# smartee_main.net
KiCad netlist of a schematic drawn in Altium Designer
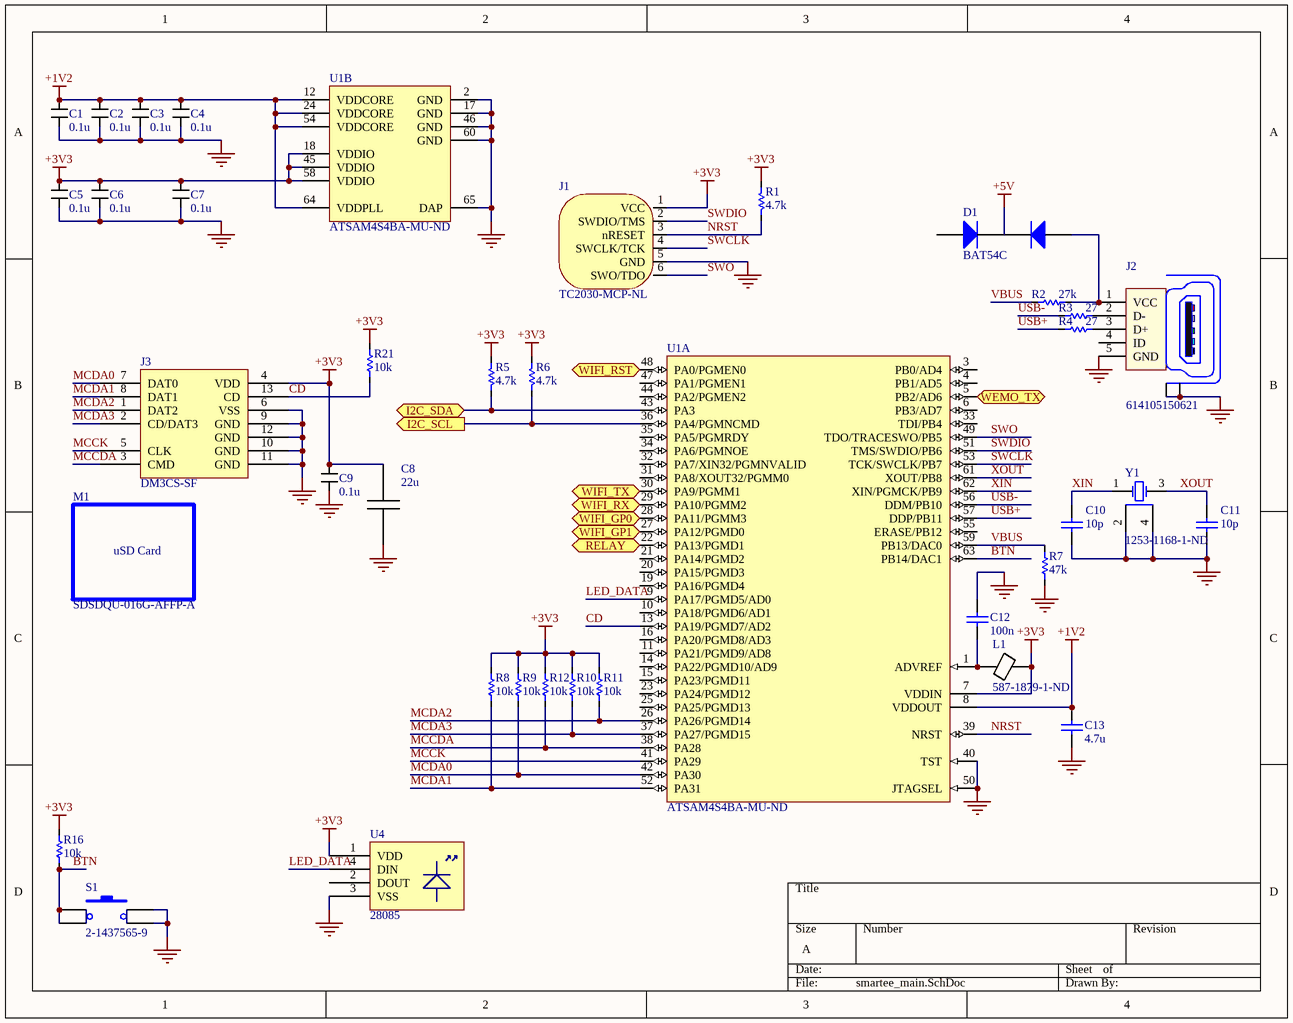
[diagram p0: smartee_main.SchDoc]

(export (version "E")
  (design (tool "Eeschema 10.0.6"))
  (components
    (comp (ref "C1")
      (value "0.1u")
      (footprint "R0603")
      (description "CAP CER 0.1UF 50V Y5V 0603")
      (fields
        (field (name "MANUFACTURER") "Yageo")
        (field (name "MANUFACTURER PART NUMBER") "CC0603ZRY5V9BB104")
      )
      (libsource (lib "NILM Library") (part "CC0603ZRY5V9BB104"))
    )
    (comp (ref "C2")
      (value "0.1u")
      (footprint "R0603")
      (description "CAP CER 0.1UF 50V Y5V 0603")
      (fields
        (field (name "MANUFACTURER") "Yageo")
        (field (name "MANUFACTURER PART NUMBER") "CC0603ZRY5V9BB104")
      )
      (libsource (lib "NILM Library") (part "CC0603ZRY5V9BB104"))
    )
    (comp (ref "C3")
      (value "0.1u")
      (footprint "R0603")
      (description "CAP CER 0.1UF 50V Y5V 0603")
      (fields
        (field (name "MANUFACTURER") "Yageo")
        (field (name "MANUFACTURER PART NUMBER") "CC0603ZRY5V9BB104")
      )
      (libsource (lib "NILM Library") (part "CC0603ZRY5V9BB104"))
    )
    (comp (ref "C4")
      (value "0.1u")
      (footprint "R0603")
      (description "CAP CER 0.1UF 50V Y5V 0603")
      (fields
        (field (name "MANUFACTURER") "Yageo")
        (field (name "MANUFACTURER PART NUMBER") "CC0603ZRY5V9BB104")
      )
      (libsource (lib "NILM Library") (part "CC0603ZRY5V9BB104"))
    )
    (comp (ref "C5")
      (value "0.1u")
      (footprint "R0603")
      (description "CAP CER 0.1UF 50V Y5V 0603")
      (fields
        (field (name "MANUFACTURER") "Yageo")
        (field (name "MANUFACTURER PART NUMBER") "CC0603ZRY5V9BB104")
      )
      (libsource (lib "NILM Library") (part "CC0603ZRY5V9BB104"))
    )
    (comp (ref "C6")
      (value "0.1u")
      (footprint "R0603")
      (description "CAP CER 0.1UF 50V Y5V 0603")
      (fields
        (field (name "MANUFACTURER") "Yageo")
        (field (name "MANUFACTURER PART NUMBER") "CC0603ZRY5V9BB104")
      )
      (libsource (lib "NILM Library") (part "CC0603ZRY5V9BB104"))
    )
    (comp (ref "C7")
      (value "0.1u")
      (footprint "R0603")
      (description "CAP CER 0.1UF 50V Y5V 0603")
      (fields
        (field (name "MANUFACTURER") "Yageo")
        (field (name "MANUFACTURER PART NUMBER") "CC0603ZRY5V9BB104")
      )
      (libsource (lib "NILM Library") (part "CC0603ZRY5V9BB104"))
    )
    (comp (ref "C8")
      (value "22u")
      (footprint "0805")
      (description "CAP CER 22UF 25V 20% X5R 0805")
      (fields
        (field (name "MANUFACTURER") "Samsung Electro-Mechanics America, Inc")
        (field (name "MANUFACTURER PART NUMBER") "CL21A226MAQNNNE")
      )
      (libsource (lib "NILM Library") (part "CL21A226MAQNNNE"))
    )
    (comp (ref "C9")
      (value "0.1u")
      (footprint "R0603")
      (description "CAP CER 0.1UF 50V Y5V 0603")
      (fields
        (field (name "MANUFACTURER") "Yageo")
        (field (name "MANUFACTURER PART NUMBER") "CC0603ZRY5V9BB104")
      )
      (libsource (lib "NILM Library") (part "CC0603ZRY5V9BB104"))
    )
    (comp (ref "C10")
      (value "10p")
      (footprint "0603")
      (description "Capacitor")
      (fields (field (name "Comment") "CAP") (field (name "PUBLISHER") "Altium Limited"))
      (libsource (lib "nilm") (part "CAP"))
    )
    (comp (ref "C11")
      (value "10p")
      (footprint "0603")
      (description "Capacitor")
      (fields (field (name "Comment") "CAP") (field (name "PUBLISHER") "Altium Limited"))
      (libsource (lib "nilm") (part "CAP"))
    )
    (comp (ref "C12")
      (value "100n")
      (footprint "0603")
      (description "Capacitor")
      (fields (field (name "Comment") "CAP") (field (name "PUBLISHER") "Altium Limited"))
      (libsource (lib "nilm") (part "CAP"))
    )
    (comp (ref "C13")
      (value "4.7u")
      (footprint "0603")
      (description "Capacitor")
      (fields (field (name "Comment") "CAP") (field (name "PUBLISHER") "Altium Limited"))
      (libsource (lib "nilm") (part "CAP"))
    )
    (comp (ref "D1")
      (value "BAT54C")
      (footprint "SOT23")
      (description "DIODE SCHOTTKY 30V 200MA SOT23")
      (fields (field (name "MANUFACTURER") "Fairchild Semiconductor"))
      (libsource (lib "NILM Library") (part "BAT54C"))
    )
    (comp (ref "J1")
      (value "TC2030-MCP-NL")
      (footprint "TC2030-MCP-NL")
      (description "Tag Connect")
      (libsource (lib "TC2030") (part "TC2030-MCP-NL"))
    )
    (comp (ref "J2")
      (value "614105150621")
      (footprint "614105150621")
      (description "CONN RCPT USB TYPE AB")
      (fields (field (name "MANUFACTURER") "Wurth Electronics Inc"))
      (libsource (lib "NILM Library") (part "614105150621"))
    )
    (comp (ref "J3")
      (value "DM3CS-SF")
      (footprint "DM3CS-SF")
      (description "CONN MICRO SD R/A HING TYPE SMD")
      (fields (field (name "MANUFACTURER") "Hirose Electric Co Ltd"))
      (libsource (lib "NILM Library") (part "DM3CS-SF"))
    )
    (comp (ref "L1")
      (value "Ferrite")
      (footprint "0603")
      (description "Ferrite bead")
      (fields
        (field (name "SUPPLIER PART NUMBER 1") "587-1879-1-ND")
        (field (name "PUBLISHER") "Altium Limited")
      )
      (libsource (lib "nilm") (part "Ferrite"))
    )
    (comp (ref "M1")
      (value "SDSDQU-016G-AFFP-A")
      (description "16 GB uSD Card")
      (libsource (lib "NILM Library") (part "uSD Card"))
    )
    (comp (ref "R1")
      (value "4.7k")
      (footprint "0603")
      (description "Resistor")
      (fields (field (name "Comment") "RES") (field (name "PUBLISHER") "Altium Limited"))
      (libsource (lib "nilm") (part "RES"))
    )
    (comp (ref "R2")
      (value "27k")
      (footprint "0603")
      (description "Resistor")
      (fields (field (name "Comment") "RES") (field (name "PUBLISHER") "Altium Limited"))
      (libsource (lib "nilm") (part "RES"))
    )
    (comp (ref "R3")
      (value "27")
      (footprint "0603")
      (description "Resistor")
      (fields (field (name "Comment") "RES") (field (name "PUBLISHER") "Altium Limited"))
      (libsource (lib "nilm") (part "RES"))
    )
    (comp (ref "R4")
      (value "27")
      (footprint "0603")
      (description "Resistor")
      (fields (field (name "Comment") "RES") (field (name "PUBLISHER") "Altium Limited"))
      (libsource (lib "nilm") (part "RES"))
    )
    (comp (ref "R5")
      (value "4.7k")
      (footprint "0603")
      (description "Resistor")
      (fields (field (name "Comment") "RES") (field (name "PUBLISHER") "Altium Limited"))
      (libsource (lib "nilm") (part "RES"))
    )
    (comp (ref "R6")
      (value "4.7k")
      (footprint "0603")
      (description "Resistor")
      (fields (field (name "Comment") "RES") (field (name "PUBLISHER") "Altium Limited"))
      (libsource (lib "nilm") (part "RES"))
    )
    (comp (ref "R7")
      (value "47k")
      (footprint "0603")
      (description "Resistor")
      (fields (field (name "Comment") "RES") (field (name "PUBLISHER") "Altium Limited"))
      (libsource (lib "nilm") (part "RES"))
    )
    (comp (ref "R8")
      (value "10k")
      (footprint "0603")
      (description "Resistor")
      (fields (field (name "Comment") "RES") (field (name "PUBLISHER") "Altium Limited"))
      (libsource (lib "nilm") (part "RES"))
    )
    (comp (ref "R9")
      (value "10k")
      (footprint "0603")
      (description "Resistor")
      (fields (field (name "Comment") "RES") (field (name "PUBLISHER") "Altium Limited"))
      (libsource (lib "nilm") (part "RES"))
    )
    (comp (ref "R10")
      (value "10k")
      (footprint "0603")
      (description "Resistor")
      (fields (field (name "Comment") "RES") (field (name "PUBLISHER") "Altium Limited"))
      (libsource (lib "nilm") (part "RES"))
    )
    (comp (ref "R11")
      (value "10k")
      (footprint "0603")
      (description "Resistor")
      (fields (field (name "Comment") "RES") (field (name "PUBLISHER") "Altium Limited"))
      (libsource (lib "nilm") (part "RES"))
    )
    (comp (ref "R12")
      (value "10k")
      (footprint "0603")
      (description "Resistor")
      (fields (field (name "Comment") "RES") (field (name "PUBLISHER") "Altium Limited"))
      (libsource (lib "nilm") (part "RES"))
    )
    (comp (ref "R16")
      (value "10k")
      (footprint "0603")
      (description "Resistor")
      (fields (field (name "Comment") "RES") (field (name "PUBLISHER") "Altium Limited"))
      (libsource (lib "nilm") (part "RES"))
    )
    (comp (ref "R21")
      (value "10k")
      (footprint "0603")
      (description "Resistor")
      (fields (field (name "Comment") "RES") (field (name "PUBLISHER") "Altium Limited"))
      (libsource (lib "nilm") (part "RES"))
    )
    (comp (ref "S1")
      (value "2-1437565-9")
      (footprint "2-1437565-9")
      (description "SWITCH TACTILE SPST-NO 0.05A 12V")
      (fields (field (name "MANUFACTURER") "TE Connectivity"))
      (libsource (lib "NILM Library") (part "2-1437565-9"))
    )
    (comp (ref "U1")
      (value "SAM4S")
      (footprint "nilm:QFN64")
      (description "Atmel SAM4S microcontroller, 64 pin")
      (fields (field (name "SUPPLIER PART NUMBER 1") "ATSAM4S4BA-MU-ND"))
      (libsource (lib "nilm") (part "SAM4S"))
    )
    (comp (ref "U4")
      (value "28085")
      (footprint "WS2812B")
      (description "WS2812 LED MODULE")
      (fields (field (name "MANUFACTURER") "Parallax Inc"))
      (libsource (lib "NILM Library") (part "28085"))
    )
    (comp (ref "Y1")
      (value "XTAL")
      (footprint "XTAL_3.2x2.5mm")
      (description "Crystal Oscillator")
      (fields
        (field (name "SUPPLIER PART NUMBER 1") "1253-1168-1-ND")
        (field (name "PUBLISHER") "Altium Limited")
      )
      (libsource (lib "nilm") (part "XTAL"))
    )
  )
  (nets
    (net (code "1") (name "+1V2") (class "Default")
      (node (ref "C1") (pin "1") (pinfunction "1_1") (pintype "passive"))
      (node (ref "C13") (pin "2") (pinfunction "2_2") (pintype "passive"))
      (node (ref "C2") (pin "1") (pinfunction "1_1") (pintype "passive"))
      (node (ref "C3") (pin "1") (pinfunction "1_1") (pintype "passive"))
      (node (ref "C4") (pin "1") (pinfunction "1_1") (pintype "passive"))
      (node (ref "U1") (pin "12") (pinfunction "VDDCORE_12") (pintype "power_in"))
      (node (ref "U1") (pin "24") (pinfunction "VDDCORE_24") (pintype "power_in"))
      (node (ref "U1") (pin "54") (pinfunction "VDDCORE_54") (pintype "power_in"))
      (node (ref "U1") (pin "64") (pinfunction "VDDPLL_64") (pintype "power_in"))
      (node (ref "U1") (pin "8") (pinfunction "VDDOUT_8") (pintype "power_in"))
    )
    (net (code "2") (name "+3V3") (class "Default")
      (node (ref "C5") (pin "1") (pinfunction "1_1") (pintype "passive"))
      (node (ref "C6") (pin "1") (pinfunction "1_1") (pintype "passive"))
      (node (ref "C7") (pin "1") (pinfunction "1_1") (pintype "passive"))
      (node (ref "C8") (pin "1") (pinfunction "1_1") (pintype "passive"))
      (node (ref "C9") (pin "1") (pinfunction "1_1") (pintype "passive"))
      (node (ref "J1") (pin "1") (pinfunction "VCC_1") (pintype "passive"))
      (node (ref "J3") (pin "4") (pinfunction "VDD_4") (pintype "passive"))
      (node (ref "L1") (pin "1") (pinfunction "1_1") (pintype "passive"))
      (node (ref "R1") (pin "1") (pinfunction "1_1") (pintype "passive"))
      (node (ref "R10") (pin "2") (pinfunction "2_2") (pintype "passive"))
      (node (ref "R11") (pin "2") (pinfunction "2_2") (pintype "passive"))
      (node (ref "R12") (pin "2") (pinfunction "2_2") (pintype "passive"))
      (node (ref "R16") (pin "2") (pinfunction "2_2") (pintype "passive"))
      (node (ref "R21") (pin "2") (pinfunction "2_2") (pintype "passive"))
      (node (ref "R5") (pin "1") (pinfunction "1_1") (pintype "passive"))
      (node (ref "R6") (pin "1") (pinfunction "1_1") (pintype "passive"))
      (node (ref "R8") (pin "2") (pinfunction "2_2") (pintype "passive"))
      (node (ref "R9") (pin "2") (pinfunction "2_2") (pintype "passive"))
      (node (ref "U1") (pin "18") (pinfunction "VDDIO_18") (pintype "power_in"))
      (node (ref "U1") (pin "45") (pinfunction "VDDIO_45") (pintype "power_in"))
      (node (ref "U1") (pin "58") (pinfunction "VDDIO_58") (pintype "power_in"))
      (node (ref "U1") (pin "7") (pinfunction "VDDIN_7") (pintype "power_in"))
      (node (ref "U4") (pin "1") (pinfunction "VDD_1") (pintype "passive"))
    )
    (net (code "3") (name "+5V") (class "Default")
      (node (ref "D1") (pin "3") (pinfunction "K_3") (pintype "passive"))
    )
    (net (code "4") (name "/BTN") (class "Default")
      (node (ref "R16") (pin "1") (pinfunction "1_1") (pintype "passive"))
      (node (ref "S1") (pin "1") (pinfunction "1_1") (pintype "passive"))
      (node (ref "S1") (pin "2") (pinfunction "2_2") (pintype "passive"))
      (node (ref "U1") (pin "63") (pinfunction "PB14/DAC1_63") (pintype "bidirectional"))
    )
    (net (code "5") (name "/CD") (class "Default")
      (node (ref "J3") (pin "13") (pinfunction "CD_13") (pintype "passive"))
      (node (ref "R21") (pin "1") (pinfunction "1_1") (pintype "passive"))
      (node (ref "U1") (pin "13") (pinfunction "PA19/PGMD7/AD2_13") (pintype "bidirectional"))
    )
    (net (code "6") (name "/I2C_SCL") (class "Default")
      (node (ref "R6") (pin "2") (pinfunction "2_2") (pintype "passive"))
      (node (ref "U1") (pin "36") (pinfunction "PA4/PGMNCMD_36") (pintype "bidirectional"))
    )
    (net (code "7") (name "/I2C_SDA") (class "Default")
      (node (ref "R5") (pin "2") (pinfunction "2_2") (pintype "passive"))
      (node (ref "U1") (pin "43") (pinfunction "PA3_43") (pintype "bidirectional"))
    )
    (net (code "8") (name "/LED_DATA") (class "Default")
      (node (ref "U1") (pin "9") (pinfunction "PA17/PGMD5/AD0_9") (pintype "bidirectional"))
      (node (ref "U4") (pin "4") (pinfunction "DIN_4") (pintype "passive"))
    )
    (net (code "9") (name "/MCCDA") (class "Default")
      (node (ref "J3") (pin "3") (pinfunction "CMD_3") (pintype "passive"))
      (node (ref "R12") (pin "1") (pinfunction "1_1") (pintype "passive"))
      (node (ref "U1") (pin "38") (pinfunction "PA28_38") (pintype "bidirectional"))
    )
    (net (code "10") (name "/MCCK") (class "Default")
      (node (ref "J3") (pin "5") (pinfunction "CLK_5") (pintype "passive"))
      (node (ref "U1") (pin "41") (pinfunction "PA29_41") (pintype "bidirectional"))
    )
    (net (code "11") (name "/MCDA0") (class "Default")
      (node (ref "J3") (pin "7") (pinfunction "DAT0_7") (pintype "passive"))
      (node (ref "R9") (pin "1") (pinfunction "1_1") (pintype "passive"))
      (node (ref "U1") (pin "42") (pinfunction "PA30_42") (pintype "bidirectional"))
    )
    (net (code "12") (name "/MCDA1") (class "Default")
      (node (ref "J3") (pin "8") (pinfunction "DAT1_8") (pintype "passive"))
      (node (ref "R8") (pin "1") (pinfunction "1_1") (pintype "passive"))
      (node (ref "U1") (pin "52") (pinfunction "PA31_52") (pintype "bidirectional"))
    )
    (net (code "13") (name "/MCDA2") (class "Default")
      (node (ref "J3") (pin "1") (pinfunction "DAT2_1") (pintype "passive"))
      (node (ref "R11") (pin "1") (pinfunction "1_1") (pintype "passive"))
      (node (ref "U1") (pin "26") (pinfunction "PA26/PGMD14_26") (pintype "bidirectional"))
    )
    (net (code "14") (name "/MCDA3") (class "Default")
      (node (ref "J3") (pin "2") (pinfunction "CD/DAT3_2") (pintype "passive"))
      (node (ref "R10") (pin "1") (pinfunction "1_1") (pintype "passive"))
      (node (ref "U1") (pin "37") (pinfunction "PA27/PGMD15_37") (pintype "bidirectional"))
    )
    (net (code "15") (name "/NRST") (class "Default")
      (node (ref "J1") (pin "3") (pinfunction "nRESET_3") (pintype "passive"))
      (node (ref "R1") (pin "2") (pinfunction "2_2") (pintype "passive"))
      (node (ref "U1") (pin "39") (pinfunction "NRST_39") (pintype "bidirectional"))
    )
    (net (code "16") (name "/RELAY") (class "Default")
      (node (ref "U1") (pin "22") (pinfunction "PA13/PGMD1_22") (pintype "bidirectional"))
    )
    (net (code "17") (name "/SWCLK") (class "Default")
      (node (ref "J1") (pin "4") (pinfunction "SWCLK/TCK_4") (pintype "passive"))
      (node (ref "U1") (pin "53") (pinfunction "TCK/SWCLK/PB7_53") (pintype "bidirectional"))
    )
    (net (code "18") (name "/SWDIO") (class "Default")
      (node (ref "J1") (pin "2") (pinfunction "SWDIO/TMS_2") (pintype "passive"))
      (node (ref "U1") (pin "51") (pinfunction "TMS/SWDIO/PB6_51") (pintype "bidirectional"))
    )
    (net (code "19") (name "/SWO") (class "Default")
      (node (ref "J1") (pin "6") (pinfunction "SWO/TDO_6") (pintype "passive"))
      (node (ref "U1") (pin "49") (pinfunction "TDO/TRACESWO/PB5_49") (pintype "bidirectional"))
    )
    (net (code "20") (name "/USB+") (class "Default")
      (node (ref "R4") (pin "1") (pinfunction "1_1") (pintype "passive"))
      (node (ref "U1") (pin "57") (pinfunction "DDP/PB11_57") (pintype "bidirectional"))
    )
    (net (code "21") (name "/USB-") (class "Default")
      (node (ref "R3") (pin "1") (pinfunction "1_1") (pintype "passive"))
      (node (ref "U1") (pin "56") (pinfunction "DDM/PB10_56") (pintype "bidirectional"))
    )
    (net (code "22") (name "/VBUS") (class "Default")
      (node (ref "R2") (pin "1") (pinfunction "1_1") (pintype "passive"))
      (node (ref "R7") (pin "2") (pinfunction "2_2") (pintype "passive"))
      (node (ref "U1") (pin "59") (pinfunction "PB13/DAC0_59") (pintype "bidirectional"))
    )
    (net (code "23") (name "/WEMO_TX") (class "Default")
      (node (ref "U1") (pin "5") (pinfunction "PB2/AD6_5") (pintype "bidirectional"))
    )
    (net (code "24") (name "/WIFI_GP0") (class "Default")
      (node (ref "U1") (pin "28") (pinfunction "PA11/PGMM3_28") (pintype "bidirectional"))
    )
    (net (code "25") (name "/WIFI_GP1") (class "Default")
      (node (ref "U1") (pin "27") (pinfunction "PA12/PGMD0_27") (pintype "bidirectional"))
    )
    (net (code "26") (name "/WIFI_RST") (class "Default")
      (node (ref "U1") (pin "48") (pinfunction "PA0/PGMEN0_48") (pintype "bidirectional"))
    )
    (net (code "27") (name "/WIFI_RX") (class "Default")
      (node (ref "U1") (pin "29") (pinfunction "PA10/PGMM2_29") (pintype "bidirectional"))
    )
    (net (code "28") (name "/WIFI_TX") (class "Default")
      (node (ref "U1") (pin "30") (pinfunction "PA9/PGMM1_30") (pintype "bidirectional"))
    )
    (net (code "29") (name "/XIN") (class "Default")
      (node (ref "C10") (pin "2") (pinfunction "2_2") (pintype "passive"))
      (node (ref "U1") (pin "62") (pinfunction "XIN/PGMCK/PB9_62") (pintype "bidirectional"))
      (node (ref "Y1") (pin "1") (pinfunction "OSC1_1") (pintype "passive"))
    )
    (net (code "30") (name "/XOUT") (class "Default")
      (node (ref "C11") (pin "2") (pinfunction "2_2") (pintype "passive"))
      (node (ref "U1") (pin "61") (pinfunction "XOUT/PB8_61") (pintype "bidirectional"))
      (node (ref "Y1") (pin "3") (pinfunction "OSC2_3") (pintype "passive"))
    )
    (net (code "31") (name "GND") (class "Default")
      (node (ref "C1") (pin "2") (pinfunction "2_2") (pintype "passive"))
      (node (ref "C10") (pin "1") (pinfunction "1_1") (pintype "passive"))
      (node (ref "C11") (pin "1") (pinfunction "1_1") (pintype "passive"))
      (node (ref "C12") (pin "2") (pinfunction "2_2") (pintype "passive"))
      (node (ref "C13") (pin "1") (pinfunction "1_1") (pintype "passive"))
      (node (ref "C2") (pin "2") (pinfunction "2_2") (pintype "passive"))
      (node (ref "C3") (pin "2") (pinfunction "2_2") (pintype "passive"))
      (node (ref "C4") (pin "2") (pinfunction "2_2") (pintype "passive"))
      (node (ref "C5") (pin "2") (pinfunction "2_2") (pintype "passive"))
      (node (ref "C6") (pin "2") (pinfunction "2_2") (pintype "passive"))
      (node (ref "C7") (pin "2") (pinfunction "2_2") (pintype "passive"))
      (node (ref "C8") (pin "2") (pinfunction "2_2") (pintype "passive"))
      (node (ref "C9") (pin "2") (pinfunction "2_2") (pintype "passive"))
      (node (ref "J1") (pin "5") (pinfunction "GND_5") (pintype "passive"))
      (node (ref "J2") (pin "5") (pinfunction "GND_5") (pintype "passive"))
      (node (ref "J2") (pin "Z1") (pinfunction "Shield_Z1") (pintype "passive"))
      (node (ref "J2") (pin "Z2") (pinfunction "Shield_Z2") (pintype "passive"))
      (node (ref "J3") (pin "10") (pinfunction "GND_10") (pintype "passive"))
      (node (ref "J3") (pin "11") (pinfunction "GND_11") (pintype "passive"))
      (node (ref "J3") (pin "12") (pinfunction "GND_12") (pintype "passive"))
      (node (ref "J3") (pin "6") (pinfunction "VSS_6") (pintype "passive"))
      (node (ref "J3") (pin "9") (pinfunction "GND_9") (pintype "passive"))
      (node (ref "R7") (pin "1") (pinfunction "1_1") (pintype "passive"))
      (node (ref "S1") (pin "3") (pinfunction "3_3") (pintype "passive"))
      (node (ref "S1") (pin "4") (pinfunction "4_4") (pintype "passive"))
      (node (ref "U1") (pin "17") (pinfunction "GND_17") (pintype "power_in"))
      (node (ref "U1") (pin "2") (pinfunction "GND_2") (pintype "power_in"))
      (node (ref "U1") (pin "40") (pinfunction "TST_40") (pintype "input"))
      (node (ref "U1") (pin "46") (pinfunction "GND_46") (pintype "power_in"))
      (node (ref "U1") (pin "50") (pinfunction "JTAGSEL_50") (pintype "input"))
      (node (ref "U1") (pin "60") (pinfunction "GND_60") (pintype "power_in"))
      (node (ref "U1") (pin "65") (pinfunction "DAP_65") (pintype "power_in"))
      (node (ref "U4") (pin "3") (pinfunction "VSS_3") (pintype "passive"))
      (node (ref "Y1") (pin "2") (pinfunction "GND_2") (pintype "passive"))
      (node (ref "Y1") (pin "4") (pinfunction "GND_4") (pintype "passive"))
    )
    (net (code "32") (name "Net-(D1-A1)") (class "Default")
      (node (ref "D1") (pin "1") (pinfunction "A1_1") (pintype "passive"))
      (node (ref "J2") (pin "1") (pinfunction "VCC_1") (pintype "passive"))
      (node (ref "R2") (pin "2") (pinfunction "2_2") (pintype "passive"))
    )
    (net (code "33") (name "Net-(J2-D+)") (class "Default")
      (node (ref "J2") (pin "3") (pinfunction "D+_3") (pintype "passive"))
      (node (ref "R4") (pin "2") (pinfunction "2_2") (pintype "passive"))
    )
    (net (code "34") (name "Net-(J2-D-)") (class "Default")
      (node (ref "J2") (pin "2") (pinfunction "D-_2") (pintype "passive"))
      (node (ref "R3") (pin "2") (pinfunction "2_2") (pintype "passive"))
    )
    (net (code "35") (name "Net-(U1A-ADVREF)") (class "Default")
      (node (ref "C12") (pin "1") (pinfunction "1_1") (pintype "passive"))
      (node (ref "L1") (pin "2") (pinfunction "2_2") (pintype "passive"))
      (node (ref "U1") (pin "1") (pinfunction "ADVREF_1") (pintype "input"))
    )
    (net (code "36") (name "unconnected-(D1-A2-Pad2)") (class "Default")
      (node (ref "D1") (pin "2") (pinfunction "A2_2") (pintype "passive"))
    )
    (net (code "37") (name "unconnected-(J2-ID-Pad4)") (class "Default")
      (node (ref "J2") (pin "4") (pinfunction "ID_4") (pintype "passive"))
    )
    (net (code "38") (name "unconnected-(U1A-ERASE{slash}PB12-Pad55)") (class "Default")
      (node (ref "U1") (pin "55") (pinfunction "ERASE/PB12_55") (pintype "bidirectional"))
    )
    (net (code "39") (name "unconnected-(U1A-PA1{slash}PGMEN1-Pad47)") (class "Default")
      (node (ref "U1") (pin "47") (pinfunction "PA1/PGMEN1_47") (pintype "bidirectional"))
    )
    (net (code "40") (name "unconnected-(U1A-PA2{slash}PGMEN2-Pad44)") (class "Default")
      (node (ref "U1") (pin "44") (pinfunction "PA2/PGMEN2_44") (pintype "bidirectional"))
    )
    (net (code "41") (name "unconnected-(U1A-PA5{slash}PGMRDY-Pad35)") (class "Default")
      (node (ref "U1") (pin "35") (pinfunction "PA5/PGMRDY_35") (pintype "bidirectional"))
    )
    (net (code "42") (name "unconnected-(U1A-PA6{slash}PGMNOE-Pad34)") (class "Default")
      (node (ref "U1") (pin "34") (pinfunction "PA6/PGMNOE_34") (pintype "bidirectional"))
    )
    (net (code "43") (name "unconnected-(U1A-PA7{slash}XIN32{slash}PGMNVALID-Pad32)") (class "Default")
      (node (ref "U1") (pin "32") (pinfunction "PA7/XIN32/PGMNVALID_32") (pintype "bidirectional"))
    )
    (net (code "44") (name "unconnected-(U1A-PA8{slash}XOUT32{slash}PGMM0-Pad31)") (class "Default")
      (node (ref "U1") (pin "31") (pinfunction "PA8/XOUT32/PGMM0_31") (pintype "bidirectional"))
    )
    (net (code "45") (name "unconnected-(U1A-PA14{slash}PGMD2-Pad21)") (class "Default")
      (node (ref "U1") (pin "21") (pinfunction "PA14/PGMD2_21") (pintype "bidirectional"))
    )
    (net (code "46") (name "unconnected-(U1A-PA15{slash}PGMD3-Pad20)") (class "Default")
      (node (ref "U1") (pin "20") (pinfunction "PA15/PGMD3_20") (pintype "bidirectional"))
    )
    (net (code "47") (name "unconnected-(U1A-PA16{slash}PGMD4-Pad19)") (class "Default")
      (node (ref "U1") (pin "19") (pinfunction "PA16/PGMD4_19") (pintype "bidirectional"))
    )
    (net (code "48") (name "unconnected-(U1A-PA18{slash}PGMD6{slash}AD1-Pad10)") (class "Default")
      (node (ref "U1") (pin "10") (pinfunction "PA18/PGMD6/AD1_10") (pintype "bidirectional"))
    )
    (net (code "49") (name "unconnected-(U1A-PA20{slash}PGMD8{slash}AD3-Pad16)") (class "Default")
      (node (ref "U1") (pin "16") (pinfunction "PA20/PGMD8/AD3_16") (pintype "bidirectional"))
    )
    (net (code "50") (name "unconnected-(U1A-PA21{slash}PGMD9{slash}AD8-Pad11)") (class "Default")
      (node (ref "U1") (pin "11") (pinfunction "PA21/PGMD9/AD8_11") (pintype "bidirectional"))
    )
    (net (code "51") (name "unconnected-(U1A-PA22{slash}PGMD10{slash}AD9-Pad14)") (class "Default")
      (node (ref "U1") (pin "14") (pinfunction "PA22/PGMD10/AD9_14") (pintype "bidirectional"))
    )
    (net (code "52") (name "unconnected-(U1A-PA23{slash}PGMD11-Pad15)") (class "Default")
      (node (ref "U1") (pin "15") (pinfunction "PA23/PGMD11_15") (pintype "bidirectional"))
    )
    (net (code "53") (name "unconnected-(U1A-PA24{slash}PGMD12-Pad23)") (class "Default")
      (node (ref "U1") (pin "23") (pinfunction "PA24/PGMD12_23") (pintype "bidirectional"))
    )
    (net (code "54") (name "unconnected-(U1A-PA25{slash}PGMD13-Pad25)") (class "Default")
      (node (ref "U1") (pin "25") (pinfunction "PA25/PGMD13_25") (pintype "bidirectional"))
    )
    (net (code "55") (name "unconnected-(U1A-PB0{slash}AD4-Pad3)") (class "Default")
      (node (ref "U1") (pin "3") (pinfunction "PB0/AD4_3") (pintype "bidirectional"))
    )
    (net (code "56") (name "unconnected-(U1A-PB1{slash}AD5-Pad4)") (class "Default")
      (node (ref "U1") (pin "4") (pinfunction "PB1/AD5_4") (pintype "bidirectional"))
    )
    (net (code "57") (name "unconnected-(U1A-PB3{slash}AD7-Pad6)") (class "Default")
      (node (ref "U1") (pin "6") (pinfunction "PB3/AD7_6") (pintype "bidirectional"))
    )
    (net (code "58") (name "unconnected-(U1A-TDI{slash}PB4-Pad33)") (class "Default")
      (node (ref "U1") (pin "33") (pinfunction "TDI/PB4_33") (pintype "bidirectional"))
    )
    (net (code "59") (name "unconnected-(U4-DOUT-Pad2)") (class "Default")
      (node (ref "U4") (pin "2") (pinfunction "DOUT_2") (pintype "passive"))
    )
  )
)
